# usb-i2c.net
KiCad netlist of a schematic drawn in EAGLE
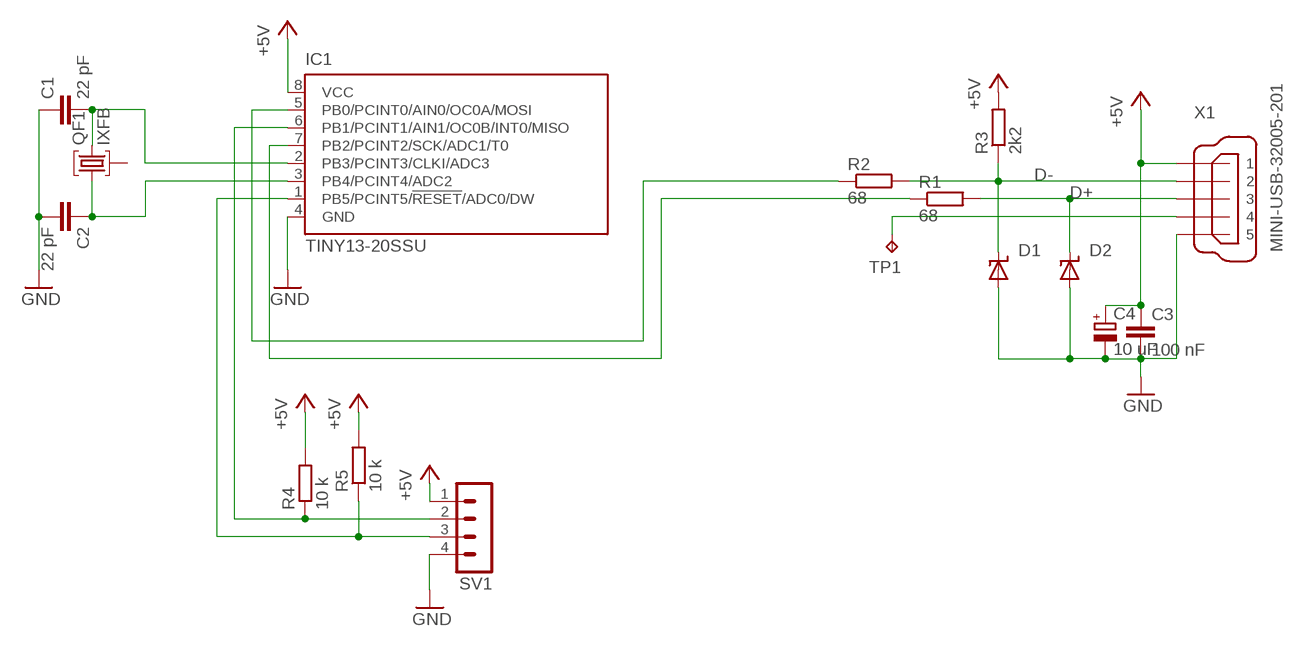
[diagram p0: schematic, sheet 1]

(export (version "E")
  (design (tool "Eeschema 10.0.6"))
  (components
    (comp (ref "C1")
      (value "22 pF")
      (footprint "eagle-import:C0603K")
      (libsource (lib "eagle-import") (part "C-EUC0603K"))
    )
    (comp (ref "C2")
      (value "22 pF")
      (footprint "eagle-import:C0603K")
      (libsource (lib "eagle-import") (part "C-EUC0603K"))
    )
    (comp (ref "C3")
      (value "100 nF")
      (footprint "eagle-import:C0603K")
      (libsource (lib "eagle-import") (part "C-EUC0603K"))
    )
    (comp (ref "C4")
      (value "10 uF")
      (footprint "eagle-import:E2,5-6E")
      (libsource (lib "eagle-import") (part "CPOL-EUE2,5-6E"))
    )
    (comp (ref "D1")
      (value "SUPPRESSOR-SMBJ")
      (footprint "eagle-import:SMBJ")
      (libsource (lib "eagle-import") (part "SUPPRESSOR-SMBJ"))
    )
    (comp (ref "D2")
      (value "SUPPRESSOR-SMBJ")
      (footprint "eagle-import:SMBJ")
      (libsource (lib "eagle-import") (part "SUPPRESSOR-SMBJ"))
    )
    (comp (ref "IC1")
      (value "TINY13-20SSU")
      (footprint "eagle-import:8S1")
      (fields (field (name "MPN") "ATTINY13-20SSU"))
      (libsource (lib "eagle-import") (part "TINY13SSU-20"))
    )
    (comp (ref "QF1")
      (value "IXFB")
      (footprint "eagle-import:UM1")
      (libsource (lib "eagle-import") (part "IXFB"))
    )
    (comp (ref "R1")
      (value "68")
      (footprint "eagle-import:R0603")
      (libsource (lib "eagle-import") (part "R-EU_R0603"))
    )
    (comp (ref "R2")
      (value "68")
      (footprint "eagle-import:R0603")
      (libsource (lib "eagle-import") (part "R-EU_R0603"))
    )
    (comp (ref "R3")
      (value "2k2")
      (footprint "eagle-import:R0603")
      (libsource (lib "eagle-import") (part "R-EU_R0603"))
    )
    (comp (ref "R4")
      (value "10 k")
      (footprint "eagle-import:R0603")
      (libsource (lib "eagle-import") (part "R-EU_R0603"))
    )
    (comp (ref "R5")
      (value "10 k")
      (footprint "eagle-import:R0603")
      (libsource (lib "eagle-import") (part "R-EU_R0603"))
    )
    (comp (ref "SV1")
      (value "MA04-1")
      (footprint "eagle-import:MA04-1")
      (libsource (lib "eagle-import") (part "MA04-1"))
    )
    (comp (ref "TP1")
      (value "TPB2,54")
      (footprint "eagle-import:B2,54")
      (libsource (lib "eagle-import") (part "TPB2,54"))
    )
    (comp (ref "X1")
      (value "MINI-USB-32005-201")
      (footprint "eagle-import:32005-201")
      (libsource (lib "eagle-import") (part "MINI-USB-32005-201"))
    )
  )
  (nets
    (net (code "1") (name "+5V") (class "Default")
      (node (ref "C3") (pin "1") (pinfunction "1_1") (pintype "passive"))
      (node (ref "C4") (pin "+") (pinfunction "+_+") (pintype "passive"))
      (node (ref "IC1") (pin "8") (pinfunction "VCC_8") (pintype "power_in"))
      (node (ref "R3") (pin "2") (pinfunction "2_2") (pintype "passive"))
      (node (ref "R4") (pin "2") (pinfunction "2_2") (pintype "passive"))
      (node (ref "R5") (pin "2") (pinfunction "2_2") (pintype "passive"))
      (node (ref "SV1") (pin "1") (pinfunction "1_1") (pintype "passive"))
      (node (ref "X1") (pin "1") (pinfunction "1_1") (pintype "passive"))
    )
    (net (code "2") (name "/D+") (class "Default")
      (node (ref "D2") (pin "C") (pinfunction "C_C") (pintype "passive"))
      (node (ref "R1") (pin "2") (pinfunction "2_2") (pintype "passive"))
      (node (ref "X1") (pin "3") (pinfunction "3_3") (pintype "passive"))
    )
    (net (code "3") (name "/D-") (class "Default")
      (node (ref "D1") (pin "C") (pinfunction "C_C") (pintype "passive"))
      (node (ref "R2") (pin "2") (pinfunction "2_2") (pintype "passive"))
      (node (ref "R3") (pin "1") (pinfunction "1_1") (pintype "passive"))
      (node (ref "X1") (pin "2") (pinfunction "2_2") (pintype "passive"))
    )
    (net (code "4") (name "GND") (class "Default")
      (node (ref "C1") (pin "1") (pinfunction "1_1") (pintype "passive"))
      (node (ref "C2") (pin "2") (pinfunction "2_2") (pintype "passive"))
      (node (ref "C3") (pin "2") (pinfunction "2_2") (pintype "passive"))
      (node (ref "C4") (pin "-") (pinfunction "-_-") (pintype "passive"))
      (node (ref "D1") (pin "A") (pinfunction "A_A") (pintype "passive"))
      (node (ref "D2") (pin "A") (pinfunction "A_A") (pintype "passive"))
      (node (ref "IC1") (pin "4") (pinfunction "GND_4") (pintype "power_in"))
      (node (ref "SV1") (pin "4") (pinfunction "4_4") (pintype "passive"))
      (node (ref "X1") (pin "5") (pinfunction "5_5") (pintype "passive"))
    )
    (net (code "5") (name "Net-(IC1-PB0{slash}PCINT0{slash}AIN0{slash}OC0A{slash}MOSI)") (class "Default")
      (node (ref "IC1") (pin "5") (pinfunction "PB0/PCINT0/AIN0/OC0A/MOSI_5") (pintype "bidirectional"))
      (node (ref "R2") (pin "1") (pinfunction "1_1") (pintype "passive"))
    )
    (net (code "6") (name "Net-(IC1-PB1{slash}PCINT1{slash}AIN1{slash}OC0B{slash}INT0{slash}MISO)") (class "Default")
      (node (ref "IC1") (pin "6") (pinfunction "PB1/PCINT1/AIN1/OC0B/INT0/MISO_6") (pintype "bidirectional"))
      (node (ref "R4") (pin "1") (pinfunction "1_1") (pintype "passive"))
      (node (ref "SV1") (pin "2") (pinfunction "2_2") (pintype "passive"))
    )
    (net (code "7") (name "Net-(IC1-PB2{slash}PCINT2{slash}SCK{slash}ADC1{slash}T0)") (class "Default")
      (node (ref "IC1") (pin "7") (pinfunction "PB2/PCINT2/SCK/ADC1/T0_7") (pintype "bidirectional"))
      (node (ref "R1") (pin "1") (pinfunction "1_1") (pintype "passive"))
    )
    (net (code "8") (name "Net-(IC1-PB3{slash}PCINT3{slash}CLKI{slash}ADC3)") (class "Default")
      (node (ref "C1") (pin "2") (pinfunction "2_2") (pintype "passive"))
      (node (ref "IC1") (pin "2") (pinfunction "PB3/PCINT3/CLKI/ADC3_2") (pintype "bidirectional"))
      (node (ref "QF1") (pin "3") (pinfunction "3_3") (pintype "passive"))
    )
    (net (code "9") (name "Net-(IC1-PB4{slash}PCINT4{slash}ADC2)") (class "Default")
      (node (ref "C2") (pin "1") (pinfunction "1_1") (pintype "passive"))
      (node (ref "IC1") (pin "3") (pinfunction "PB4/PCINT4/ADC2_3") (pintype "bidirectional"))
      (node (ref "QF1") (pin "1") (pinfunction "1_1") (pintype "passive"))
    )
    (net (code "10") (name "Net-(IC1-PB5{slash}PCINT5{slash}~{RESET}{slash}ADC0{slash}DW)") (class "Default")
      (node (ref "IC1") (pin "1") (pinfunction "PB5/PCINT5/~{RESET}/ADC0/DW_1") (pintype "bidirectional"))
      (node (ref "R5") (pin "1") (pinfunction "1_1") (pintype "passive"))
      (node (ref "SV1") (pin "3") (pinfunction "3_3") (pintype "passive"))
    )
    (net (code "11") (name "Net-(TP1-PadTP)") (class "Default")
      (node (ref "TP1") (pin "TP") (pinfunction "TP_TP") (pintype "input"))
      (node (ref "X1") (pin "4") (pinfunction "4_4") (pintype "passive"))
    )
    (net (code "12") (name "unconnected-(QF1-Pad2)") (class "Default")
      (node (ref "QF1") (pin "2") (pinfunction "2_2") (pintype "passive"))
    )
  )
)
